# jetson_nano_breakout.net
KiCad netlist of a schematic drawn in Altium Designer
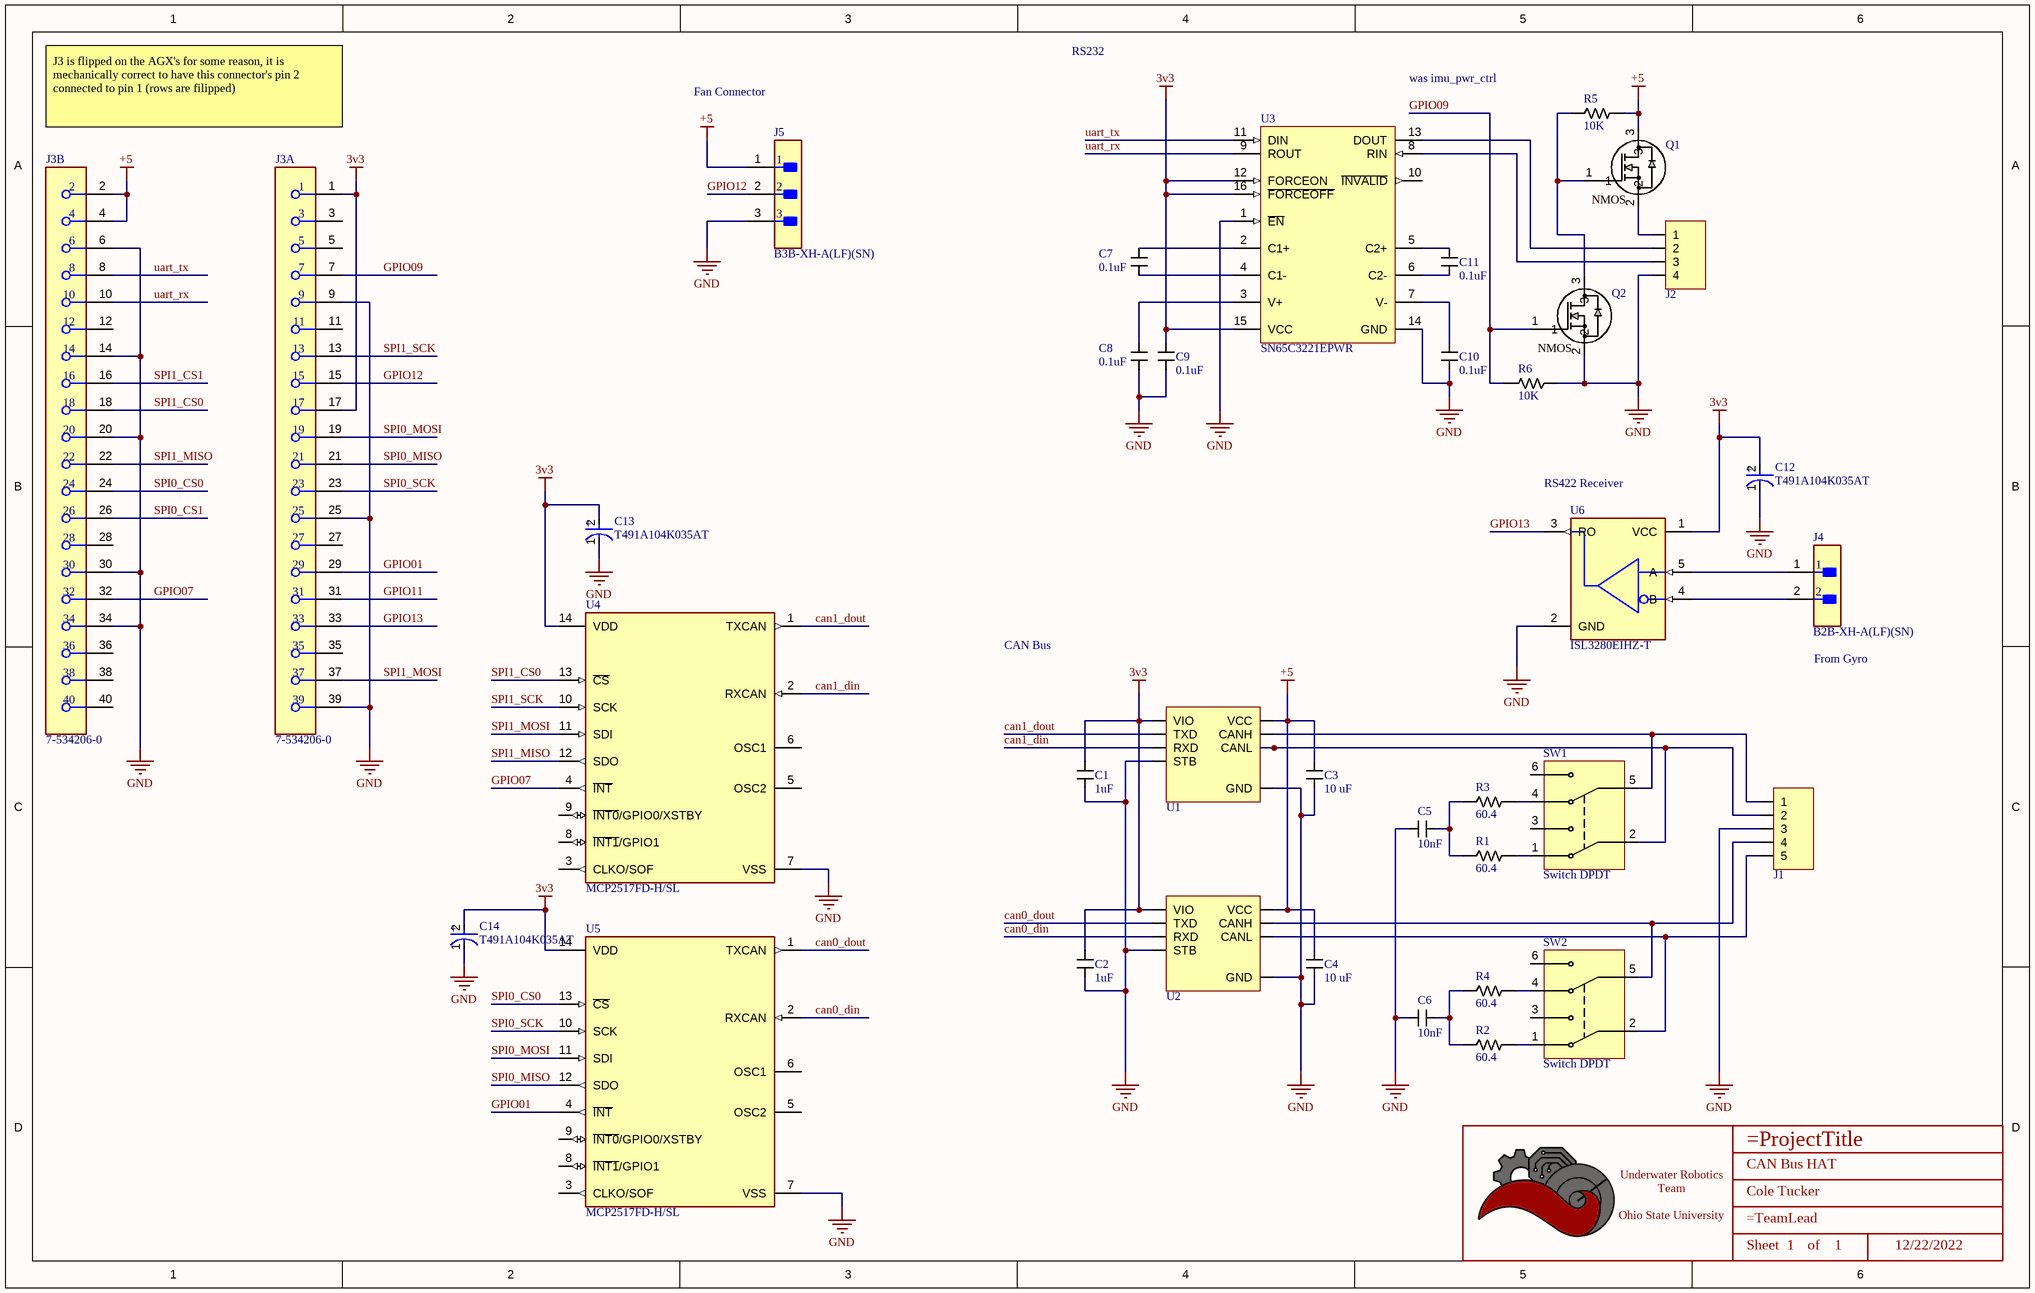
[diagram p0: jetson_nano_breakout.SchDoc]

(export (version "E")
  (design (tool "Eeschema 10.0.6"))
  (components
    (comp (ref "*")
      (value "Title_Block")
      (footprint "LOGO")
      (description "UWRT Schematic Title Block Template\r\n\r\nCreated June 2021, Dylan Trainor")
      (libsource (lib "UWRT") (part "Title_Block"))
    )
    (comp (ref "C1")
      (value "1uF")
      (footprint "CAPACITOR_0603")
      (description "Cap 1uF 16V +/-10%\r\nCeramic 0603")
      (fields
        (field (name "TOLERANCE") "+/- 10%")
        (field (name "VOLTAGE") "16V")
        (field (name "MADE BY") "Flip B")
      )
      (libsource (lib "Capacitors") (part "CAPACITOR_1uF_0603"))
    )
    (comp (ref "C2")
      (value "1uF")
      (footprint "CAPACITOR_0603")
      (description "Cap 1uF 16V +/-10%\r\nCeramic 0603")
      (fields
        (field (name "TOLERANCE") "+/- 10%")
        (field (name "VOLTAGE") "16V")
        (field (name "MADE BY") "Flip B")
      )
      (libsource (lib "Capacitors") (part "CAPACITOR_1uF_0603"))
    )
    (comp (ref "C3")
      (value "10uF Ceramic 6.3V")
      (footprint "CAPACITOR_0603")
      (description "Cap 10uF 6.3V +/-20%\r\nCeramic 0603")
      (fields
        (field (name "TOLERANCE") "+/- 20%")
        (field (name "VOLTAGE") "6.3V")
        (field (name "VALUE (UF)") "10 uF")
        (field (name "MADE BY") "Flip B")
      )
      (libsource (lib "Capacitors") (part "CAPACITOR_10uF_0603"))
    )
    (comp (ref "C4")
      (value "10uF Ceramic 6.3V")
      (footprint "CAPACITOR_0603")
      (description "Cap 10uF 6.3V +/-20%\r\nCeramic 0603")
      (fields
        (field (name "TOLERANCE") "+/- 20%")
        (field (name "VOLTAGE") "6.3V")
        (field (name "VALUE (UF)") "10 uF")
        (field (name "MADE BY") "Flip B")
      )
      (libsource (lib "Capacitors") (part "CAPACITOR_10uF_0603"))
    )
    (comp (ref "C5")
      (value "10nF")
      (footprint "CAPACITOR_0603")
      (description "Cap 10nF 6.3V +/-20%\r\nCeramic 0603")
      (fields
        (field (name "TOLERANCE") "+/- 10%")
        (field (name "VOLTAGE") "6.3V")
        (field (name "MADE BY") "Flip B")
      )
      (libsource (lib "Capacitors") (part "CAPACITOR_0.01uF_0603"))
    )
    (comp (ref "C6")
      (value "10nF")
      (footprint "CAPACITOR_0603")
      (description "Cap 10nF 6.3V +/-20%\r\nCeramic 0603")
      (fields
        (field (name "TOLERANCE") "+/- 10%")
        (field (name "VOLTAGE") "6.3V")
        (field (name "MADE BY") "Flip B")
      )
      (libsource (lib "Capacitors") (part "CAPACITOR_0.01uF_0603"))
    )
    (comp (ref "C7")
      (value "0.1uF")
      (footprint "CAPACITOR_0603")
      (description "Cap 100nF 6.3V +/-10%\r\nCeramic 0603")
      (fields
        (field (name "TOLERANCE") "+/- 10%")
        (field (name "VOLTAGE") "6.3V")
        (field (name "MADE BY") "Flip B")
      )
      (libsource (lib "Capacitors") (part "CAPACITOR_0.1uF_0603"))
    )
    (comp (ref "C8")
      (value "0.1uF")
      (footprint "CAPACITOR_0603")
      (description "Cap 100nF 6.3V +/-10%\r\nCeramic 0603")
      (fields
        (field (name "TOLERANCE") "+/- 10%")
        (field (name "VOLTAGE") "6.3V")
        (field (name "MADE BY") "Flip B")
      )
      (libsource (lib "Capacitors") (part "CAPACITOR_0.1uF_0603"))
    )
    (comp (ref "C9")
      (value "0.1uF")
      (footprint "CAPACITOR_0603")
      (description "Cap 100nF 6.3V +/-10%\r\nCeramic 0603")
      (fields
        (field (name "TOLERANCE") "+/- 10%")
        (field (name "VOLTAGE") "6.3V")
        (field (name "MADE BY") "Flip B")
      )
      (libsource (lib "Capacitors") (part "CAPACITOR_0.1uF_0603"))
    )
    (comp (ref "C10")
      (value "0.1uF")
      (footprint "CAPACITOR_0603")
      (description "Cap 100nF 6.3V +/-10%\r\nCeramic 0603")
      (fields
        (field (name "TOLERANCE") "+/- 10%")
        (field (name "VOLTAGE") "6.3V")
        (field (name "MADE BY") "Flip B")
      )
      (libsource (lib "Capacitors") (part "CAPACITOR_0.1uF_0603"))
    )
    (comp (ref "C11")
      (value "0.1uF")
      (footprint "CAPACITOR_0603")
      (description "Cap 100nF 6.3V +/-10%\r\nCeramic 0603")
      (fields
        (field (name "TOLERANCE") "+/- 10%")
        (field (name "VOLTAGE") "6.3V")
        (field (name "MADE BY") "Flip B")
      )
      (libsource (lib "Capacitors") (part "CAPACITOR_0.1uF_0603"))
    )
    (comp (ref "C12")
      (value "T491A104K035AT")
      (footprint "FP-T491A104K035AT-MFG")
      (description "CAP TANT 0.1UF 10% 35V 1206")
      (fields (field (name "TOLERANCE") "10%") (field (name "VOLTAGE") "35V"))
      (libsource (lib "Altium Content Vault") (part "a00bbbee19879c290e62620ae7e47b1"))
    )
    (comp (ref "C13")
      (value "T491A104K035AT")
      (footprint "FP-T491A104K035AT-MFG")
      (description "CAP TANT 0.1UF 10% 35V 1206")
      (fields (field (name "TOLERANCE") "10%") (field (name "VOLTAGE") "35V"))
      (libsource (lib "Altium Content Vault") (part "a00bbbee19879c290e62620ae7e47b1"))
    )
    (comp (ref "C14")
      (value "T491A104K035AT")
      (footprint "FP-T491A104K035AT-MFG")
      (description "CAP TANT 0.1UF 10% 35V 1206")
      (fields (field (name "TOLERANCE") "10%") (field (name "VOLTAGE") "35V"))
      (libsource (lib "Altium Content Vault") (part "a00bbbee19879c290e62620ae7e47b1"))
    )
    (comp (ref "J1")
      (value "XH2.54 VERT")
      (footprint "CONN_JST_XH254_5POS_VERT")
      (description "JST XH 2.54mm Pitch 5 Pos Vertical")
      (fields (field (name "MANUFACTURER") "JST") (field (name "CREATED BY") "Robert P"))
      (libsource (lib "Connectors") (part "CONN_JST_XH254_5POS_VERT"))
    )
    (comp (ref "J2")
      (value "XH2.54 VERT")
      (footprint "CONN_JST_XH254_4POS_VERT")
      (description "JST XH 2.54mm Pitch 4 Pos Vertical")
      (fields (field (name "MANUFACTURER") "JST") (field (name "CREATED BY") "Robert P"))
      (libsource (lib "Connectors") (part "CONN_JST_XH254_4POS_VERT"))
    )
    (comp (ref "J3")
      (value "7-534206-0")
      (footprint "FP-7-534206-0-MFG")
      (description "CONN RCPT 40POS 0.1 GOLD PCB")
      (fields
        (field (name "MANUFACTURER") "TE Connectivity")
        (field (name "OCTOPART") "https://octopart.com/7-534206-0-te+connectivity-39516831")
      )
      (libsource (lib "Altium Content Vault") (part "7acf1c4a8db21028d11741a46a6ec78"))
    )
    (comp (ref "J4")
      (value "B2B-XH-A(LF)(SN)")
      (footprint "FP-B2B-XH-A_LF_SN-MFG")
      (description "CONN HEADER VERT 2POS 2.5MM")
      (libsource (lib "Altium Content Vault") (part "3bc925449376181038e59eaffc5286c"))
    )
    (comp (ref "J5")
      (value "B3B-XH-A(LF)(SN)")
      (footprint "FP-B3B-XH-A_LF_SN-MFG")
      (description "CONN HEADER VERT 3POS 2.5MM")
      (libsource (lib "Altium Content Vault") (part "0d3f023dd272f625e17a2be33dea85f"))
    )
    (comp (ref "Q1")
      (value "MOSFET N-CH 30V 5.8A SOT-23-3")
      (footprint "SOT-23-3")
      (description "N-Channel 30 V 5.8A (Ta) 1.4W (Ta) Surface Mount SOT-23-3")
      (fields (field (name "MANUFACTURER _PART_NUMBER") "AO3404A") (field (name "CREATED BY") "Dylan T"))
      (libsource (lib "Transistors") (part "AO3404A"))
    )
    (comp (ref "Q2")
      (value "MOSFET N-CH 30V 5.8A SOT-23-3")
      (footprint "SOT-23-3")
      (description "N-Channel 30 V 5.8A (Ta) 1.4W (Ta) Surface Mount SOT-23-3")
      (fields (field (name "MANUFACTURER _PART_NUMBER") "AO3404A") (field (name "CREATED BY") "Dylan T"))
      (libsource (lib "Transistors") (part "AO3404A"))
    )
    (comp (ref "R1")
      (value "60.4 Ohm 1% 1/16W")
      (footprint "RESISTOR_0402")
      (description "RES 60.4 OHM 1% 1/16W 0402")
      (fields
        (field (name "TOLERANCE") "+/- 1%")
        (field (name "VALUE  (OHMS)") "60.4")
        (field (name "MADE BY") "Robert Pafford")
      )
      (libsource (lib "Resistors") (part "RESISTOR_60.4_0402"))
    )
    (comp (ref "R2")
      (value "60.4 Ohm 1% 1/16W")
      (footprint "RESISTOR_0402")
      (description "RES 60.4 OHM 1% 1/16W 0402")
      (fields
        (field (name "TOLERANCE") "+/- 1%")
        (field (name "VALUE  (OHMS)") "60.4")
        (field (name "MADE BY") "Robert Pafford")
      )
      (libsource (lib "Resistors") (part "RESISTOR_60.4_0402"))
    )
    (comp (ref "R3")
      (value "60.4 Ohm 1% 1/16W")
      (footprint "RESISTOR_0402")
      (description "RES 60.4 OHM 1% 1/16W 0402")
      (fields
        (field (name "TOLERANCE") "+/- 1%")
        (field (name "VALUE  (OHMS)") "60.4")
        (field (name "MADE BY") "Robert Pafford")
      )
      (libsource (lib "Resistors") (part "RESISTOR_60.4_0402"))
    )
    (comp (ref "R4")
      (value "60.4 Ohm 1% 1/16W")
      (footprint "RESISTOR_0402")
      (description "RES 60.4 OHM 1% 1/16W 0402")
      (fields
        (field (name "TOLERANCE") "+/- 1%")
        (field (name "VALUE  (OHMS)") "60.4")
        (field (name "MADE BY") "Robert Pafford")
      )
      (libsource (lib "Resistors") (part "RESISTOR_60.4_0402"))
    )
    (comp (ref "R5")
      (value "10k Ohm 5% 1/10W")
      (footprint "RESISTOR_0603")
      (description "RES 10k OHM 5% 1/10W 0603")
      (fields
        (field (name "TOLERANCE") "+/- 5%")
        (field (name "VALUE  (OHMS)") "10K")
        (field (name "MADE BY") "Robert Pafford")
      )
      (libsource (lib "Resistors") (part "RESISTOR_10K_0603"))
    )
    (comp (ref "R6")
      (value "10k Ohm 5% 1/10W")
      (footprint "RESISTOR_0603")
      (description "RES 10k OHM 5% 1/10W 0603")
      (fields
        (field (name "TOLERANCE") "+/- 5%")
        (field (name "VALUE  (OHMS)") "10K")
        (field (name "MADE BY") "Robert Pafford")
      )
      (libsource (lib "Resistors") (part "RESISTOR_10K_0603"))
    )
    (comp (ref "SW1")
      (value "Switch DPDT")
      (footprint "CAS-220TA")
      (description "GOLD SWITCH FLUSH SLIDE DPDT 100MA 6V")
      (fields (field (name "MADE BY") "Robert Pafford"))
      (libsource (lib "Switches") (part "CAS-220TA_CAN_TERM"))
    )
    (comp (ref "SW2")
      (value "Switch DPDT")
      (footprint "CAS-220TA")
      (description "GOLD SWITCH FLUSH SLIDE DPDT 100MA 6V")
      (fields (field (name "MADE BY") "Robert Pafford"))
      (libsource (lib "Switches") (part "CAS-220TA_CAN_TERM"))
    )
    (comp (ref "U1")
      (value "CAN Transceiver")
      (footprint "SOIC-8")
      (description "CAN Interface IC High-Speed CAN Transceiver with Standby Mode")
      (fields (field (name "MADE BY") "Robert Pafford"))
      (libsource (lib "Integrated Circuits") (part "TJA1442AT"))
    )
    (comp (ref "U2")
      (value "CAN Transceiver")
      (footprint "SOIC-8")
      (description "CAN Interface IC High-Speed CAN Transceiver with Standby Mode")
      (fields (field (name "MADE BY") "Robert Pafford"))
      (libsource (lib "Integrated Circuits") (part "TJA1442AT"))
    )
    (comp (ref "U3")
      (value "SN65C3221EPWR")
      (footprint "PW0016A_M")
      (libsource (lib "Altium Content Vault") (part "TI-SN65C3221E-TSSOP_PW-16"))
    )
    (comp (ref "U4")
      (value "MCP2517FD-H/SL")
      (footprint "FP-C04-065-SL-MFG")
      (description "CANbus Controller CAN 2.0 SPI Interface 14-SOIC")
      (fields (field (name "MANUFACTURER") "Microchip"))
      (libsource (lib "Altium Content Vault") (part "008caafe10a874835a82fe443bcfa61"))
    )
    (comp (ref "U5")
      (value "MCP2517FD-H/SL")
      (footprint "FP-C04-065-SL-MFG")
      (description "CANbus Controller CAN 2.0 SPI Interface 14-SOIC")
      (fields (field (name "MANUFACTURER") "Microchip"))
      (libsource (lib "Altium Content Vault") (part "008caafe10a874835a82fe443bcfa61"))
    )
    (comp (ref "U6")
      (value "ISL3280EIHZ-T")
      (footprint "FP-P5_064-MFG")
      (description "IC RCVR ESD RS485/422 LP SOT23-5")
      (fields
        (field (name "MANUFACTURER") "Renesas")
        (field (name "OCTOPART") "https://octopart.com/isl3280eihz-t-renesas-88254858")
      )
      (libsource (lib "Altium Content Vault") (part "dfcd02365d4109d45b3bc98e27c58b4"))
    )
  )
  (nets
    (net (code "1") (name "+5") (class "Default")
      (node (ref "C3") (pin "1") (pinfunction "1_1") (pintype "passive"))
      (node (ref "C4") (pin "1") (pinfunction "1_1") (pintype "passive"))
      (node (ref "J3") (pin "2") (pinfunction "2_2") (pintype "passive"))
      (node (ref "J3") (pin "4") (pinfunction "4_4") (pintype "passive"))
      (node (ref "J5") (pin "1") (pinfunction "1_1") (pintype "passive"))
      (node (ref "Q1") (pin "3") (pinfunction "3_3") (pintype "passive"))
      (node (ref "R5") (pin "1") (pinfunction "1_1") (pintype "passive"))
      (node (ref "U1") (pin "3") (pinfunction "VCC_3") (pintype "passive"))
      (node (ref "U2") (pin "3") (pinfunction "VCC_3") (pintype "passive"))
    )
    (net (code "2") (name "/GPIO01") (class "Default")
      (node (ref "J3") (pin "29") (pinfunction "29_29") (pintype "passive"))
      (node (ref "U5") (pin "4") (pinfunction "~{INT}_4") (pintype "output"))
    )
    (net (code "3") (name "/GPIO07") (class "Default")
      (node (ref "J3") (pin "32") (pinfunction "32_32") (pintype "passive"))
      (node (ref "U4") (pin "4") (pinfunction "~{INT}_4") (pintype "output"))
    )
    (net (code "4") (name "/GPIO09") (class "Default")
      (node (ref "J3") (pin "7") (pinfunction "7_7") (pintype "passive"))
      (node (ref "Q2") (pin "1") (pinfunction "1_1") (pintype "passive"))
      (node (ref "R6") (pin "1") (pinfunction "1_1") (pintype "passive"))
    )
    (net (code "5") (name "/GPIO11") (class "Default")
      (node (ref "J3") (pin "31") (pinfunction "31_31") (pintype "passive"))
    )
    (net (code "6") (name "/GPIO12") (class "Default")
      (node (ref "J3") (pin "15") (pinfunction "15_15") (pintype "passive"))
      (node (ref "J5") (pin "2") (pinfunction "2_2") (pintype "passive"))
    )
    (net (code "7") (name "/GPIO13") (class "Default")
      (node (ref "J3") (pin "33") (pinfunction "33_33") (pintype "passive"))
      (node (ref "U6") (pin "3") (pinfunction "RO_3") (pintype "output"))
    )
    (net (code "8") (name "/SPI0_CS0") (class "Default")
      (node (ref "J3") (pin "24") (pinfunction "24_24") (pintype "passive"))
      (node (ref "U5") (pin "13") (pinfunction "~{CS}_13") (pintype "input"))
    )
    (net (code "9") (name "/SPI0_CS1") (class "Default")
      (node (ref "J3") (pin "26") (pinfunction "26_26") (pintype "passive"))
    )
    (net (code "10") (name "/SPI0_MISO") (class "Default")
      (node (ref "J3") (pin "21") (pinfunction "21_21") (pintype "passive"))
      (node (ref "U5") (pin "12") (pinfunction "SDO_12") (pintype "output"))
    )
    (net (code "11") (name "/SPI0_MOSI") (class "Default")
      (node (ref "J3") (pin "19") (pinfunction "19_19") (pintype "passive"))
      (node (ref "U5") (pin "11") (pinfunction "SDI_11") (pintype "input"))
    )
    (net (code "12") (name "/SPI0_SCK") (class "Default")
      (node (ref "J3") (pin "23") (pinfunction "23_23") (pintype "passive"))
      (node (ref "U5") (pin "10") (pinfunction "SCK_10") (pintype "input"))
    )
    (net (code "13") (name "/SPI1_CS0") (class "Default")
      (node (ref "J3") (pin "18") (pinfunction "18_18") (pintype "passive"))
      (node (ref "U4") (pin "13") (pinfunction "~{CS}_13") (pintype "input"))
    )
    (net (code "14") (name "/SPI1_CS1") (class "Default")
      (node (ref "J3") (pin "16") (pinfunction "16_16") (pintype "passive"))
    )
    (net (code "15") (name "/SPI1_MISO") (class "Default")
      (node (ref "J3") (pin "22") (pinfunction "22_22") (pintype "passive"))
      (node (ref "U4") (pin "12") (pinfunction "SDO_12") (pintype "output"))
    )
    (net (code "16") (name "/SPI1_MOSI") (class "Default")
      (node (ref "J3") (pin "37") (pinfunction "37_37") (pintype "passive"))
      (node (ref "U4") (pin "11") (pinfunction "SDI_11") (pintype "input"))
    )
    (net (code "17") (name "/SPI1_SCK") (class "Default")
      (node (ref "J3") (pin "13") (pinfunction "13_13") (pintype "passive"))
      (node (ref "U4") (pin "10") (pinfunction "SCK_10") (pintype "input"))
    )
    (net (code "18") (name "/can0_din") (class "Default")
      (node (ref "U2") (pin "4") (pinfunction "RXD_4") (pintype "passive"))
      (node (ref "U5") (pin "2") (pinfunction "RXCAN_2") (pintype "input"))
    )
    (net (code "19") (name "/can0_dout") (class "Default")
      (node (ref "U2") (pin "1") (pinfunction "TXD_1") (pintype "passive"))
      (node (ref "U5") (pin "1") (pinfunction "TXCAN_1") (pintype "output"))
    )
    (net (code "20") (name "/can1_din") (class "Default")
      (node (ref "U1") (pin "4") (pinfunction "RXD_4") (pintype "passive"))
      (node (ref "U4") (pin "2") (pinfunction "RXCAN_2") (pintype "input"))
    )
    (net (code "21") (name "/can1_dout") (class "Default")
      (node (ref "U1") (pin "1") (pinfunction "TXD_1") (pintype "passive"))
      (node (ref "U4") (pin "1") (pinfunction "TXCAN_1") (pintype "output"))
    )
    (net (code "22") (name "/uart_rx") (class "Default")
      (node (ref "J3") (pin "10") (pinfunction "10_10") (pintype "passive"))
      (node (ref "U3") (pin "9") (pinfunction "ROUT_9") (pintype "tri_state"))
    )
    (net (code "23") (name "/uart_tx") (class "Default")
      (node (ref "J3") (pin "8") (pinfunction "8_8") (pintype "passive"))
      (node (ref "U3") (pin "11") (pinfunction "DIN_11") (pintype "input"))
    )
    (net (code "24") (name "3v3") (class "Default")
      (node (ref "C1") (pin "1") (pinfunction "1_1") (pintype "passive"))
      (node (ref "C12") (pin "2") (pinfunction "A_2") (pintype "passive"))
      (node (ref "C13") (pin "2") (pinfunction "A_2") (pintype "passive"))
      (node (ref "C14") (pin "2") (pinfunction "A_2") (pintype "passive"))
      (node (ref "C2") (pin "1") (pinfunction "1_1") (pintype "passive"))
      (node (ref "C9") (pin "1") (pinfunction "1_1") (pintype "passive"))
      (node (ref "J3") (pin "1") (pinfunction "1_1") (pintype "passive"))
      (node (ref "J3") (pin "17") (pinfunction "17_17") (pintype "passive"))
      (node (ref "U1") (pin "5") (pinfunction "VIO_5") (pintype "passive"))
      (node (ref "U2") (pin "5") (pinfunction "VIO_5") (pintype "passive"))
      (node (ref "U3") (pin "12") (pinfunction "FORCEON_12") (pintype "input"))
      (node (ref "U3") (pin "15") (pinfunction "VCC_15") (pintype "power_in"))
      (node (ref "U3") (pin "16") (pinfunction "~{FORCEOFF}_16") (pintype "input"))
      (node (ref "U4") (pin "14") (pinfunction "VDD_14") (pintype "power_in"))
      (node (ref "U5") (pin "14") (pinfunction "VDD_14") (pintype "power_in"))
      (node (ref "U6") (pin "1") (pinfunction "VCC_1") (pintype "power_in"))
    )
    (net (code "25") (name "GND") (class "Default")
      (node (ref "C1") (pin "2") (pinfunction "2_2") (pintype "passive"))
      (node (ref "C10") (pin "2") (pinfunction "2_2") (pintype "passive"))
      (node (ref "C12") (pin "1") (pinfunction "C_1") (pintype "passive"))
      (node (ref "C13") (pin "1") (pinfunction "C_1") (pintype "passive"))
      (node (ref "C14") (pin "1") (pinfunction "C_1") (pintype "passive"))
      (node (ref "C2") (pin "2") (pinfunction "2_2") (pintype "passive"))
      (node (ref "C3") (pin "2") (pinfunction "2_2") (pintype "passive"))
      (node (ref "C4") (pin "2") (pinfunction "2_2") (pintype "passive"))
      (node (ref "C5") (pin "1") (pinfunction "1_1") (pintype "passive"))
      (node (ref "C6") (pin "1") (pinfunction "1_1") (pintype "passive"))
      (node (ref "C8") (pin "2") (pinfunction "2_2") (pintype "passive"))
      (node (ref "C9") (pin "2") (pinfunction "2_2") (pintype "passive"))
      (node (ref "J1") (pin "3") (pinfunction "3_3") (pintype "passive"))
      (node (ref "J2") (pin "4") (pinfunction "4_4") (pintype "passive"))
      (node (ref "J3") (pin "14") (pinfunction "14_14") (pintype "passive"))
      (node (ref "J3") (pin "20") (pinfunction "20_20") (pintype "passive"))
      (node (ref "J3") (pin "25") (pinfunction "25_25") (pintype "passive"))
      (node (ref "J3") (pin "30") (pinfunction "30_30") (pintype "passive"))
      (node (ref "J3") (pin "34") (pinfunction "34_34") (pintype "passive"))
      (node (ref "J3") (pin "39") (pinfunction "39_39") (pintype "passive"))
      (node (ref "J3") (pin "6") (pinfunction "6_6") (pintype "passive"))
      (node (ref "J3") (pin "9") (pinfunction "9_9") (pintype "passive"))
      (node (ref "J5") (pin "3") (pinfunction "3_3") (pintype "passive"))
      (node (ref "Q2") (pin "2") (pinfunction "2_2") (pintype "passive"))
      (node (ref "R6") (pin "2") (pinfunction "2_2") (pintype "passive"))
      (node (ref "U1") (pin "2") (pinfunction "GND_2") (pintype "passive"))
      (node (ref "U1") (pin "8") (pinfunction "STB_8") (pintype "passive"))
      (node (ref "U2") (pin "2") (pinfunction "GND_2") (pintype "passive"))
      (node (ref "U2") (pin "8") (pinfunction "STB_8") (pintype "passive"))
      (node (ref "U3") (pin "1") (pinfunction "~{EN}_1") (pintype "input"))
      (node (ref "U3") (pin "14") (pinfunction "GND_14") (pintype "power_in"))
      (node (ref "U4") (pin "7") (pinfunction "VSS_7") (pintype "power_in"))
      (node (ref "U5") (pin "7") (pinfunction "VSS_7") (pintype "power_in"))
      (node (ref "U6") (pin "2") (pinfunction "GND_2") (pintype "power_in"))
    )
    (net (code "26") (name "Net-(C5-Pad2)") (class "Default")
      (node (ref "C5") (pin "2") (pinfunction "2_2") (pintype "passive"))
      (node (ref "R1") (pin "2") (pinfunction "2_2") (pintype "passive"))
      (node (ref "R3") (pin "2") (pinfunction "2_2") (pintype "passive"))
    )
    (net (code "27") (name "Net-(C6-Pad2)") (class "Default")
      (node (ref "C6") (pin "2") (pinfunction "2_2") (pintype "passive"))
      (node (ref "R2") (pin "2") (pinfunction "2_2") (pintype "passive"))
      (node (ref "R4") (pin "2") (pinfunction "2_2") (pintype "passive"))
    )
    (net (code "28") (name "Net-(J2-Pad1)") (class "Default")
      (node (ref "J2") (pin "1") (pinfunction "1_1") (pintype "passive"))
      (node (ref "Q1") (pin "2") (pinfunction "2_2") (pintype "passive"))
    )
    (net (code "29") (name "Net-(Q1-Pad1)") (class "Default")
      (node (ref "Q1") (pin "1") (pinfunction "1_1") (pintype "passive"))
      (node (ref "Q2") (pin "3") (pinfunction "3_3") (pintype "passive"))
      (node (ref "R5") (pin "2") (pinfunction "2_2") (pintype "passive"))
    )
    (net (code "30") (name "Net-(R1-Pad1)") (class "Default")
      (node (ref "R1") (pin "1") (pinfunction "1_1") (pintype "passive"))
      (node (ref "SW1") (pin "1") (pintype "passive"))
    )
    (net (code "31") (name "Net-(R2-Pad1)") (class "Default")
      (node (ref "R2") (pin "1") (pinfunction "1_1") (pintype "passive"))
      (node (ref "SW2") (pin "1") (pintype "passive"))
    )
    (net (code "32") (name "Net-(R3-Pad1)") (class "Default")
      (node (ref "R3") (pin "1") (pinfunction "1_1") (pintype "passive"))
      (node (ref "SW1") (pin "4") (pintype "passive"))
    )
    (net (code "33") (name "Net-(R4-Pad1)") (class "Default")
      (node (ref "R4") (pin "1") (pinfunction "1_1") (pintype "passive"))
      (node (ref "SW2") (pin "4") (pintype "passive"))
    )
    (net (code "34") (name "Net-(U1-CANH)") (class "Default")
      (node (ref "J1") (pin "1") (pinfunction "1_1") (pintype "passive"))
      (node (ref "SW1") (pin "5") (pintype "passive"))
      (node (ref "U1") (pin "7") (pinfunction "CANH_7") (pintype "passive"))
    )
    (net (code "35") (name "Net-(U1-CANL)") (class "Default")
      (node (ref "J1") (pin "2") (pinfunction "2_2") (pintype "passive"))
      (node (ref "SW1") (pin "2") (pintype "passive"))
      (node (ref "U1") (pin "6") (pinfunction "CANL_6") (pintype "passive"))
    )
    (net (code "36") (name "Net-(U2-CANH)") (class "Default")
      (node (ref "J1") (pin "4") (pinfunction "4_4") (pintype "passive"))
      (node (ref "SW2") (pin "5") (pintype "passive"))
      (node (ref "U2") (pin "7") (pinfunction "CANH_7") (pintype "passive"))
    )
    (net (code "37") (name "Net-(U2-CANL)") (class "Default")
      (node (ref "J1") (pin "5") (pinfunction "5_5") (pintype "passive"))
      (node (ref "SW2") (pin "2") (pintype "passive"))
      (node (ref "U2") (pin "6") (pinfunction "CANL_6") (pintype "passive"))
    )
    (net (code "38") (name "Net-(U3-C1+)") (class "Default")
      (node (ref "C7") (pin "1") (pinfunction "1_1") (pintype "passive"))
      (node (ref "U3") (pin "2") (pinfunction "C1+_2") (pintype "passive"))
    )
    (net (code "39") (name "Net-(U3-C1-)") (class "Default")
      (node (ref "C7") (pin "2") (pinfunction "2_2") (pintype "passive"))
      (node (ref "U3") (pin "4") (pinfunction "C1-_4") (pintype "passive"))
    )
    (net (code "40") (name "Net-(U3-C2+)") (class "Default")
      (node (ref "C11") (pin "1") (pinfunction "1_1") (pintype "passive"))
      (node (ref "U3") (pin "5") (pinfunction "C2+_5") (pintype "passive"))
    )
    (net (code "41") (name "Net-(U3-C2-)") (class "Default")
      (node (ref "C11") (pin "2") (pinfunction "2_2") (pintype "passive"))
      (node (ref "U3") (pin "6") (pinfunction "C2-_6") (pintype "passive"))
    )
    (net (code "42") (name "Net-(U3-DOUT)") (class "Default")
      (node (ref "J2") (pin "2") (pinfunction "2_2") (pintype "passive"))
      (node (ref "U3") (pin "13") (pinfunction "DOUT_13") (pintype "tri_state"))
    )
    (net (code "43") (name "Net-(U3-RIN)") (class "Default")
      (node (ref "J2") (pin "3") (pinfunction "3_3") (pintype "passive"))
      (node (ref "U3") (pin "8") (pinfunction "RIN_8") (pintype "input"))
    )
    (net (code "44") (name "Net-(U3-V+)") (class "Default")
      (node (ref "C8") (pin "1") (pinfunction "1_1") (pintype "passive"))
      (node (ref "U3") (pin "3") (pinfunction "V+_3") (pintype "power_in"))
    )
    (net (code "45") (name "Net-(U3-V-)") (class "Default")
      (node (ref "C10") (pin "1") (pinfunction "1_1") (pintype "passive"))
      (node (ref "U3") (pin "7") (pinfunction "V-_7") (pintype "power_in"))
    )
    (net (code "46") (name "Net-(U6-A)") (class "Default")
      (node (ref "J4") (pin "1") (pinfunction "1_1") (pintype "passive"))
      (node (ref "U6") (pin "5") (pinfunction "A_5") (pintype "input"))
    )
    (net (code "47") (name "Net-(U6-B)") (class "Default")
      (node (ref "J4") (pin "2") (pinfunction "2_2") (pintype "passive"))
      (node (ref "U6") (pin "4") (pinfunction "B_4") (pintype "input"))
    )
    (net (code "48") (name "unconnected-(J3-Pad3)") (class "Default")
      (node (ref "J3") (pin "3") (pinfunction "3_3") (pintype "passive"))
    )
    (net (code "49") (name "unconnected-(J3-Pad5)") (class "Default")
      (node (ref "J3") (pin "5") (pinfunction "5_5") (pintype "passive"))
    )
    (net (code "50") (name "unconnected-(J3-Pad11)") (class "Default")
      (node (ref "J3") (pin "11") (pinfunction "11_11") (pintype "passive"))
    )
    (net (code "51") (name "unconnected-(J3-Pad12)") (class "Default")
      (node (ref "J3") (pin "12") (pinfunction "12_12") (pintype "passive"))
    )
    (net (code "52") (name "unconnected-(J3-Pad27)") (class "Default")
      (node (ref "J3") (pin "27") (pinfunction "27_27") (pintype "passive"))
    )
    (net (code "53") (name "unconnected-(J3-Pad28)") (class "Default")
      (node (ref "J3") (pin "28") (pinfunction "28_28") (pintype "passive"))
    )
    (net (code "54") (name "unconnected-(J3-Pad35)") (class "Default")
      (node (ref "J3") (pin "35") (pinfunction "35_35") (pintype "passive"))
    )
    (net (code "55") (name "unconnected-(J3-Pad36)") (class "Default")
      (node (ref "J3") (pin "36") (pinfunction "36_36") (pintype "passive"))
    )
    (net (code "56") (name "unconnected-(J3-Pad38)") (class "Default")
      (node (ref "J3") (pin "38") (pinfunction "38_38") (pintype "passive"))
    )
    (net (code "57") (name "unconnected-(J3-Pad40)") (class "Default")
      (node (ref "J3") (pin "40") (pinfunction "40_40") (pintype "passive"))
    )
    (net (code "58") (name "unconnected-(SW1-Pad3)") (class "Default")
      (node (ref "SW1") (pin "3") (pintype "passive"))
    )
    (net (code "59") (name "unconnected-(SW1-Pad6)") (class "Default")
      (node (ref "SW1") (pin "6") (pintype "passive"))
    )
    (net (code "60") (name "unconnected-(SW2-Pad3)") (class "Default")
      (node (ref "SW2") (pin "3") (pintype "passive"))
    )
    (net (code "61") (name "unconnected-(SW2-Pad6)") (class "Default")
      (node (ref "SW2") (pin "6") (pintype "passive"))
    )
    (net (code "62") (name "unconnected-(U3-~{INVALID}-Pad10)") (class "Default")
      (node (ref "U3") (pin "10") (pinfunction "~{INVALID}_10") (pintype "output"))
    )
    (net (code "63") (name "unconnected-(U4-CLKO{slash}SOF-Pad3)") (class "Default")
      (node (ref "U4") (pin "3") (pinfunction "CLKO/SOF_3") (pintype "output"))
    )
    (net (code "64") (name "unconnected-(U4-OSC1-Pad6)") (class "Default")
      (node (ref "U4") (pin "6") (pinfunction "OSC1_6") (pintype "passive"))
    )
    (net (code "65") (name "unconnected-(U4-OSC2-Pad5)") (class "Default")
      (node (ref "U4") (pin "5") (pinfunction "OSC2_5") (pintype "passive"))
    )
    (net (code "66") (name "unconnected-(U4-~{INT0}{slash}GPIO0{slash}XSTBY-Pad9)") (class "Default")
      (node (ref "U4") (pin "9") (pinfunction "~{INT0}/GPIO0/XSTBY_9") (pintype "bidirectional"))
    )
    (net (code "67") (name "unconnected-(U4-~{INT1}{slash}GPIO1-Pad8)") (class "Default")
      (node (ref "U4") (pin "8") (pinfunction "~{INT1}/GPIO1_8") (pintype "bidirectional"))
    )
    (net (code "68") (name "unconnected-(U5-CLKO{slash}SOF-Pad3)") (class "Default")
      (node (ref "U5") (pin "3") (pinfunction "CLKO/SOF_3") (pintype "output"))
    )
    (net (code "69") (name "unconnected-(U5-OSC1-Pad6)") (class "Default")
      (node (ref "U5") (pin "6") (pinfunction "OSC1_6") (pintype "passive"))
    )
    (net (code "70") (name "unconnected-(U5-OSC2-Pad5)") (class "Default")
      (node (ref "U5") (pin "5") (pinfunction "OSC2_5") (pintype "passive"))
    )
    (net (code "71") (name "unconnected-(U5-~{INT0}{slash}GPIO0{slash}XSTBY-Pad9)") (class "Default")
      (node (ref "U5") (pin "9") (pinfunction "~{INT0}/GPIO0/XSTBY_9") (pintype "bidirectional"))
    )
    (net (code "72") (name "unconnected-(U5-~{INT1}{slash}GPIO1-Pad8)") (class "Default")
      (node (ref "U5") (pin "8") (pinfunction "~{INT1}/GPIO1_8") (pintype "bidirectional"))
    )
  )
)
